# rv_pwr_es_relay.net
KiCad netlist of a schematic drawn in Altium Designer
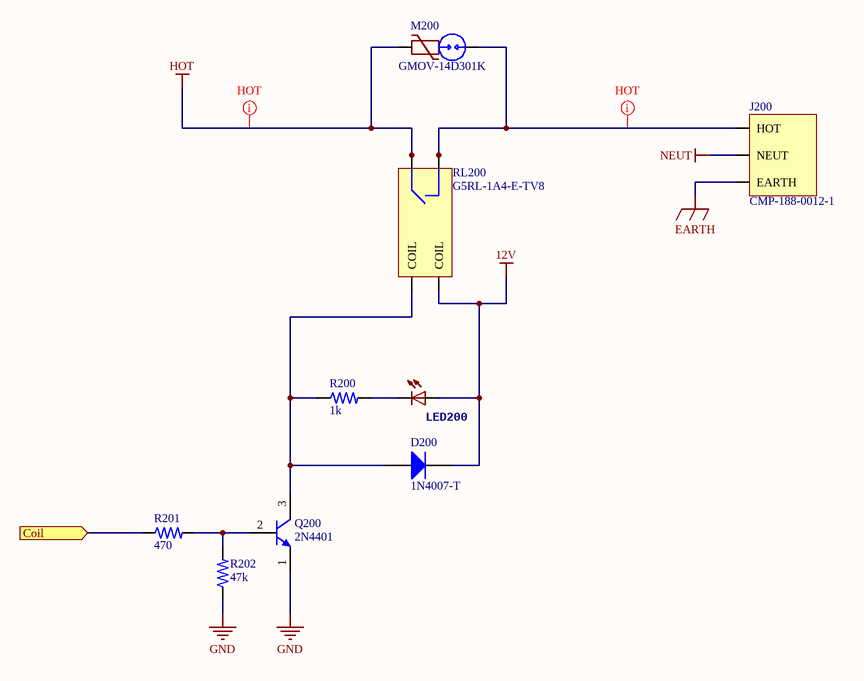
[diagram p0: rv_pwr_es_relay.SchDoc]

(export (version "E")
  (design (tool "Eeschema 10.0.6"))
  (components
    (comp (ref "D200")
      (value "1N4007-T")
      (footprint "DIOD-DO-41-P-2_V2")
      (description "VR=1000V IF=1A 8pF")
      (libsource (lib "StackFoundry LLC") (part "DIOD-D-A1K2-2"))
    )
    (comp (ref "J200")
      (value "CMP-188-0012-1")
      (footprint "3-213598-2")
      (fields (field (name "SOURCE") "con-tyco.SCHLIB"))
      (libsource (lib "StackFoundry LLC") (part "3-213598-2"))
    )
    (comp (ref "LED200") (value "~") (footprint "LED5MM") (libsource (lib "general") (part "LED5MM")))
    (comp (ref "M200")
      (value "GMOV-14D301K")
      (footprint "GMOV_14mm")
      (libsource (lib "StackFoundry LLC") (part "GMOV"))
    )
    (comp (ref "Q200")
      (value "2N4401")
      (footprint "ONSC-TO-92-3-29-11")
      (description "Transistor NPN Silicon 40V IC=600ma TO-92 Case General Purpose Amplifier And Switch")
      (fields (field (name "MF") "Rectron"))
      (libsource (lib "StackFoundry LLC") (part "ONSC-NPN-E1B2C3-3"))
    )
    (comp (ref "R200")
      (value "1k")
      (footprint "0207/10")
      (description "Res Carbon Film 1K Ohm 5% 1/4W -500ppm/°C to 350ppm/°C Conformal AXL Thru-Hole Paper T/R")
      (fields (field (name "Comment") "1k TH 0207 5% 0.25W"))
      (libsource (lib "StackFoundry LLC") (part "R-US"))
    )
    (comp (ref "R201")
      (value "470")
      (footprint "0207/10")
      (description "Res Carbon Film 470 Ohm 5% 1/4W -500ppm/°C to 350ppm/°C Conformal AXL Thru-Hole Paper T/R")
      (fields (field (name "Comment") "470 TH 0207 5% 0.25W"))
      (libsource (lib "StackFoundry LLC") (part "R-US"))
    )
    (comp (ref "R202")
      (value "47k")
      (footprint "0207/10 - Cloned")
      (description "Res Carbon Film 47K Ohm 5% 1/4W -500ppm/°C to 350ppm/°C Conformal AXL Thru-Hole Paper T/R")
      (fields (field (name "Comment") "47k TH 0207 5% 1/4W"))
      (libsource (lib "StackFoundry LLC") (part "R-US"))
    )
    (comp (ref "RL200")
      (value "G5RL-1A4-E-TV8")
      (footprint "G5RL-1A4-E-TV8")
      (libsource (lib "StackFoundry LLC") (part "RelaySPST_DT"))
    )
  )
  (nets
    (net (code "1") (name "/Coil") (class "Default")
      (node (ref "R201") (pin "1") (pinfunction "1_1") (pintype "passive"))
    )
    (net (code "2") (name "12V") (class "Default")
      (node (ref "D200") (pin "2") (pinfunction "K_2") (pintype "passive"))
      (node (ref "LED200") (pin "A") (pinfunction "A_A") (pintype "passive"))
      (node (ref "RL200") (pin "1") (pinfunction "COIL_1") (pintype "passive"))
    )
    (net (code "3") (name "EARTH") (class "Default")
      (node (ref "J200") (pin "3") (pinfunction "EARTH_3") (pintype "passive"))
    )
    (net (code "4") (name "GND") (class "Default")
      (node (ref "Q200") (pin "1") (pinfunction "E_1") (pintype "passive"))
      (node (ref "R202") (pin "1") (pinfunction "1_1") (pintype "passive"))
    )
    (net (code "5") (name "HOT") (class "Default")
      (node (ref "M200") (pin "1") (pinfunction "P$1_1") (pintype "passive"))
      (node (ref "RL200") (pin "4") (pintype "passive"))
      (node (ref "RL200") (pin "5") (pintype "passive"))
    )
    (net (code "6") (name "NEUT") (class "Default")
      (node (ref "J200") (pin "1") (pinfunction "NEUT_1") (pintype "passive"))
    )
    (net (code "7") (name "Net-(D200-A)") (class "Default")
      (node (ref "D200") (pin "1") (pinfunction "A_1") (pintype "passive"))
      (node (ref "Q200") (pin "3") (pinfunction "C_3") (pintype "passive"))
      (node (ref "R200") (pin "1") (pinfunction "1_1") (pintype "passive"))
      (node (ref "RL200") (pin "8") (pinfunction "COIL_8") (pintype "passive"))
    )
    (net (code "8") (name "Net-(J200-HOT)") (class "Default")
      (node (ref "J200") (pin "2") (pinfunction "HOT_2") (pintype "passive"))
      (node (ref "M200") (pin "2") (pinfunction "P$2_2") (pintype "passive"))
      (node (ref "RL200") (pin "3") (pintype "passive"))
      (node (ref "RL200") (pin "6") (pintype "passive"))
    )
    (net (code "9") (name "Net-(LED200-C)") (class "Default")
      (node (ref "LED200") (pin "K") (pinfunction "C_K") (pintype "passive"))
      (node (ref "R200") (pin "2") (pinfunction "2_2") (pintype "passive"))
    )
    (net (code "10") (name "Net-(Q200-B)") (class "Default")
      (node (ref "Q200") (pin "2") (pinfunction "B_2") (pintype "passive"))
      (node (ref "R201") (pin "2") (pinfunction "2_2") (pintype "passive"))
      (node (ref "R202") (pin "2") (pinfunction "2_2") (pintype "passive"))
    )
  )
)
